# sismin.net
KiCad netlist of a schematic drawn in EAGLE
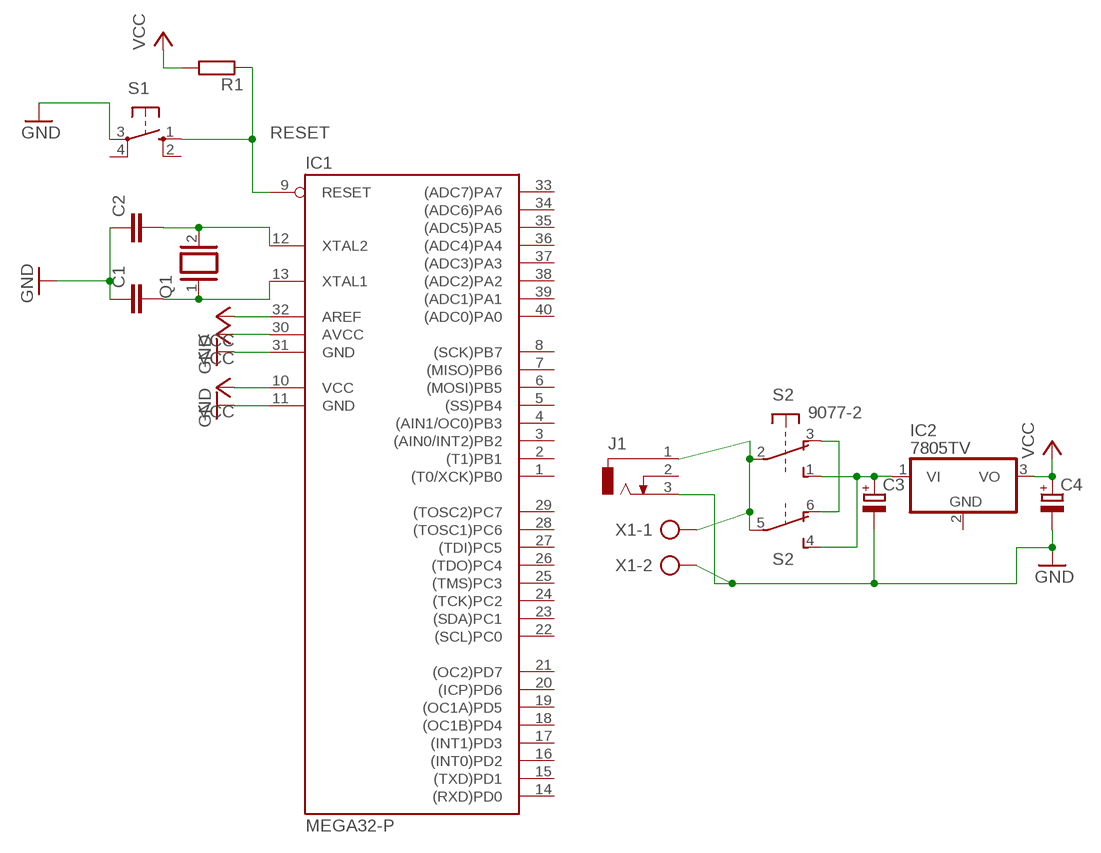
[diagram p0: schematic, sheet 1]

(export (version "E")
  (design (tool "Eeschema 10.0.6"))
  (components
    (comp (ref "C1")
      (value "C-EU025-025X050")
      (footprint "eagle-import:C025-025X050")
      (libsource (lib "eagle-import") (part "C-EU025-025X050"))
    )
    (comp (ref "C2")
      (value "C-EU025-025X050")
      (footprint "eagle-import:C025-025X050")
      (libsource (lib "eagle-import") (part "C-EU025-025X050"))
    )
    (comp (ref "C3")
      (value "CPOL-EUE2.5-5")
      (footprint "eagle-import:E2,5-5")
      (libsource (lib "eagle-import") (part "CPOL-EUE2.5-5"))
    )
    (comp (ref "C4")
      (value "CPOL-EUE2.5-5")
      (footprint "eagle-import:E2,5-5")
      (libsource (lib "eagle-import") (part "CPOL-EUE2.5-5"))
    )
    (comp (ref "IC1")
      (value "MEGA32-P")
      (footprint "eagle-import:DIL40")
      (fields (field (name "MPN") "ATMEGA32-16PU"))
      (libsource (lib "eagle-import") (part "MEGA32-P"))
    )
    (comp (ref "IC2")
      (value "7805TV")
      (footprint "eagle-import:TO220V")
      (libsource (lib "eagle-import") (part "78TV05"))
    )
    (comp (ref "J1")
      (value "DCJ0303")
      (footprint "eagle-import:DCJ0303")
      (libsource (lib "eagle-import") (part "DCJ0303"))
    )
    (comp (ref "Q1")
      (value "XTAL/S")
      (footprint "eagle-import:QS")
      (libsource (lib "eagle-import") (part "XTAL/S"))
    )
    (comp (ref "R1")
      (value "R-EU_0204/7")
      (footprint "eagle-import:0204_7")
      (libsource (lib "eagle-import") (part "R-EU_0204/7"))
    )
    (comp (ref "S1")
      (value "10-XX")
      (footprint "eagle-import:B3F-10XX")
      (fields (field (name "MPN") "B3F-1000"))
      (libsource (lib "eagle-import") (part "10-XX"))
    )
    (comp (ref "S2")
      (value "9077-2")
      (footprint "eagle-import:9077-2")
      (libsource (lib "eagle-import") (part "9077-2"))
    )
    (comp (ref "X1")
      (value "AK300/2")
      (footprint "eagle-import:AK300_2")
      (libsource (lib "eagle-import") (part "AK300/2"))
    )
  )
  (nets
    (net (code "1") (name "/RESET") (class "Default")
      (node (ref "IC1") (pin "9") (pinfunction "RESET_9") (pintype "input"))
      (node (ref "R1") (pin "1") (pinfunction "1_1") (pintype "passive"))
      (node (ref "S1") (pin "1") (pinfunction "S_1") (pintype "passive"))
    )
    (net (code "2") (name "GND") (class "Default")
      (node (ref "C1") (pin "1") (pinfunction "1_1") (pintype "passive"))
      (node (ref "C2") (pin "1") (pinfunction "1_1") (pintype "passive"))
      (node (ref "C3") (pin "-") (pinfunction "-_-") (pintype "passive"))
      (node (ref "C4") (pin "-") (pinfunction "-_-") (pintype "passive"))
      (node (ref "IC1") (pin "11") (pinfunction "GND_11") (pintype "power_in"))
      (node (ref "IC1") (pin "31") (pinfunction "GND_31") (pintype "power_in"))
      (node (ref "J1") (pin "3") (pinfunction "3_3") (pintype "passive"))
      (node (ref "S1") (pin "3") (pinfunction "P_3") (pintype "passive"))
      (node (ref "X1") (pin "2") (pinfunction "KL_2") (pintype "passive"))
    )
    (net (code "3") (name "Net-(IC1-XTAL1)") (class "Default")
      (node (ref "C1") (pin "2") (pinfunction "2_2") (pintype "passive"))
      (node (ref "IC1") (pin "13") (pinfunction "XTAL1_13") (pintype "bidirectional"))
      (node (ref "Q1") (pin "1") (pinfunction "1_1") (pintype "passive"))
    )
    (net (code "4") (name "Net-(IC1-XTAL2)") (class "Default")
      (node (ref "C2") (pin "2") (pinfunction "2_2") (pintype "passive"))
      (node (ref "IC1") (pin "12") (pinfunction "XTAL2_12") (pintype "bidirectional"))
      (node (ref "Q1") (pin "2") (pinfunction "2_2") (pintype "passive"))
    )
    (net (code "5") (name "Net-(IC2-VI)") (class "Default")
      (node (ref "C3") (pin "+") (pinfunction "+_+") (pintype "passive"))
      (node (ref "IC2") (pin "1") (pinfunction "VI_1") (pintype "input"))
      (node (ref "S2") (pin "1") (pinfunction "S_1") (pintype "passive"))
      (node (ref "S2") (pin "4") (pinfunction "S_4") (pintype "passive"))
    )
    (net (code "6") (name "Net-(S2A-O)") (class "Default")
      (node (ref "S2") (pin "3") (pinfunction "O_3") (pintype "passive"))
      (node (ref "S2") (pin "6") (pinfunction "O_6") (pintype "passive"))
    )
    (net (code "7") (name "Net-(S2A-P)") (class "Default")
      (node (ref "J1") (pin "1") (pinfunction "1_1") (pintype "passive"))
      (node (ref "S2") (pin "2") (pinfunction "P_2") (pintype "passive"))
      (node (ref "S2") (pin "5") (pinfunction "P_5") (pintype "passive"))
      (node (ref "X1") (pin "1") (pinfunction "KL_1") (pintype "passive"))
    )
    (net (code "8") (name "VCC") (class "Default")
      (node (ref "C4") (pin "+") (pinfunction "+_+") (pintype "passive"))
      (node (ref "IC1") (pin "10") (pinfunction "VCC_10") (pintype "power_in"))
      (node (ref "IC1") (pin "30") (pinfunction "AVCC_30") (pintype "power_in"))
      (node (ref "IC1") (pin "32") (pinfunction "AREF_32") (pintype "passive"))
      (node (ref "IC2") (pin "3") (pinfunction "VO_3") (pintype "passive"))
      (node (ref "R1") (pin "2") (pinfunction "2_2") (pintype "passive"))
    )
    (net (code "9") (name "unconnected-(IC1-(ADC0)PA0-Pad40)") (class "Default")
      (node (ref "IC1") (pin "40") (pinfunction "(ADC0)PA0_40") (pintype "bidirectional"))
    )
    (net (code "10") (name "unconnected-(IC1-(ADC1)PA1-Pad39)") (class "Default")
      (node (ref "IC1") (pin "39") (pinfunction "(ADC1)PA1_39") (pintype "bidirectional"))
    )
    (net (code "11") (name "unconnected-(IC1-(ADC2)PA2-Pad38)") (class "Default")
      (node (ref "IC1") (pin "38") (pinfunction "(ADC2)PA2_38") (pintype "bidirectional"))
    )
    (net (code "12") (name "unconnected-(IC1-(ADC3)PA3-Pad37)") (class "Default")
      (node (ref "IC1") (pin "37") (pinfunction "(ADC3)PA3_37") (pintype "bidirectional"))
    )
    (net (code "13") (name "unconnected-(IC1-(ADC4)PA4-Pad36)") (class "Default")
      (node (ref "IC1") (pin "36") (pinfunction "(ADC4)PA4_36") (pintype "bidirectional"))
    )
    (net (code "14") (name "unconnected-(IC1-(ADC5)PA5-Pad35)") (class "Default")
      (node (ref "IC1") (pin "35") (pinfunction "(ADC5)PA5_35") (pintype "bidirectional"))
    )
    (net (code "15") (name "unconnected-(IC1-(ADC6)PA6-Pad34)") (class "Default")
      (node (ref "IC1") (pin "34") (pinfunction "(ADC6)PA6_34") (pintype "bidirectional"))
    )
    (net (code "16") (name "unconnected-(IC1-(ADC7)PA7-Pad33)") (class "Default")
      (node (ref "IC1") (pin "33") (pinfunction "(ADC7)PA7_33") (pintype "bidirectional"))
    )
    (net (code "17") (name "unconnected-(IC1-(AIN0{slash}INT2)PB2-Pad3)") (class "Default")
      (node (ref "IC1") (pin "3") (pinfunction "(AIN0/INT2)PB2_3") (pintype "bidirectional"))
    )
    (net (code "18") (name "unconnected-(IC1-(AIN1{slash}OC0)PB3-Pad4)") (class "Default")
      (node (ref "IC1") (pin "4") (pinfunction "(AIN1/OC0)PB3_4") (pintype "bidirectional"))
    )
    (net (code "19") (name "unconnected-(IC1-(ICP)PD6-Pad20)") (class "Default")
      (node (ref "IC1") (pin "20") (pinfunction "(ICP)PD6_20") (pintype "bidirectional"))
    )
    (net (code "20") (name "unconnected-(IC1-(INT0)PD2-Pad16)") (class "Default")
      (node (ref "IC1") (pin "16") (pinfunction "(INT0)PD2_16") (pintype "bidirectional"))
    )
    (net (code "21") (name "unconnected-(IC1-(INT1)PD3-Pad17)") (class "Default")
      (node (ref "IC1") (pin "17") (pinfunction "(INT1)PD3_17") (pintype "bidirectional"))
    )
    (net (code "22") (name "unconnected-(IC1-(MISO)PB6-Pad7)") (class "Default")
      (node (ref "IC1") (pin "7") (pinfunction "(MISO)PB6_7") (pintype "bidirectional"))
    )
    (net (code "23") (name "unconnected-(IC1-(MOSI)PB5-Pad6)") (class "Default")
      (node (ref "IC1") (pin "6") (pinfunction "(MOSI)PB5_6") (pintype "bidirectional"))
    )
    (net (code "24") (name "unconnected-(IC1-(OC1A)PD5-Pad19)") (class "Default")
      (node (ref "IC1") (pin "19") (pinfunction "(OC1A)PD5_19") (pintype "bidirectional"))
    )
    (net (code "25") (name "unconnected-(IC1-(OC1B)PD4-Pad18)") (class "Default")
      (node (ref "IC1") (pin "18") (pinfunction "(OC1B)PD4_18") (pintype "bidirectional"))
    )
    (net (code "26") (name "unconnected-(IC1-(OC2)PD7-Pad21)") (class "Default")
      (node (ref "IC1") (pin "21") (pinfunction "(OC2)PD7_21") (pintype "bidirectional"))
    )
    (net (code "27") (name "unconnected-(IC1-(RXD)PD0-Pad14)") (class "Default")
      (node (ref "IC1") (pin "14") (pinfunction "(RXD)PD0_14") (pintype "bidirectional"))
    )
    (net (code "28") (name "unconnected-(IC1-(SCK)PB7-Pad8)") (class "Default")
      (node (ref "IC1") (pin "8") (pinfunction "(SCK)PB7_8") (pintype "bidirectional"))
    )
    (net (code "29") (name "unconnected-(IC1-(SCL)PC0-Pad22)") (class "Default")
      (node (ref "IC1") (pin "22") (pinfunction "(SCL)PC0_22") (pintype "bidirectional"))
    )
    (net (code "30") (name "unconnected-(IC1-(SDA)PC1-Pad23)") (class "Default")
      (node (ref "IC1") (pin "23") (pinfunction "(SDA)PC1_23") (pintype "bidirectional"))
    )
    (net (code "31") (name "unconnected-(IC1-(SS)PB4-Pad5)") (class "Default")
      (node (ref "IC1") (pin "5") (pinfunction "(SS)PB4_5") (pintype "bidirectional"))
    )
    (net (code "32") (name "unconnected-(IC1-(T0{slash}XCK)PB0-Pad1)") (class "Default")
      (node (ref "IC1") (pin "1") (pinfunction "(T0/XCK)PB0_1") (pintype "bidirectional"))
    )
    (net (code "33") (name "unconnected-(IC1-(T1)PB1-Pad2)") (class "Default")
      (node (ref "IC1") (pin "2") (pinfunction "(T1)PB1_2") (pintype "bidirectional"))
    )
    (net (code "34") (name "unconnected-(IC1-(TCK)PC2-Pad24)") (class "Default")
      (node (ref "IC1") (pin "24") (pinfunction "(TCK)PC2_24") (pintype "bidirectional"))
    )
    (net (code "35") (name "unconnected-(IC1-(TDI)PC5-Pad27)") (class "Default")
      (node (ref "IC1") (pin "27") (pinfunction "(TDI)PC5_27") (pintype "bidirectional"))
    )
    (net (code "36") (name "unconnected-(IC1-(TDO)PC4-Pad26)") (class "Default")
      (node (ref "IC1") (pin "26") (pinfunction "(TDO)PC4_26") (pintype "bidirectional"))
    )
    (net (code "37") (name "unconnected-(IC1-(TMS)PC3-Pad25)") (class "Default")
      (node (ref "IC1") (pin "25") (pinfunction "(TMS)PC3_25") (pintype "bidirectional"))
    )
    (net (code "38") (name "unconnected-(IC1-(TOSC1)PC6-Pad28)") (class "Default")
      (node (ref "IC1") (pin "28") (pinfunction "(TOSC1)PC6_28") (pintype "bidirectional"))
    )
    (net (code "39") (name "unconnected-(IC1-(TOSC2)PC7-Pad29)") (class "Default")
      (node (ref "IC1") (pin "29") (pinfunction "(TOSC2)PC7_29") (pintype "bidirectional"))
    )
    (net (code "40") (name "unconnected-(IC1-(TXD)PD1-Pad15)") (class "Default")
      (node (ref "IC1") (pin "15") (pinfunction "(TXD)PD1_15") (pintype "bidirectional"))
    )
    (net (code "41") (name "unconnected-(IC2-GND-Pad2)") (class "Default")
      (node (ref "IC2") (pin "2") (pinfunction "GND_2") (pintype "passive"))
    )
    (net (code "42") (name "unconnected-(J1-Pad2)") (class "Default")
      (node (ref "J1") (pin "2") (pinfunction "2_2") (pintype "passive"))
    )
    (net (code "43") (name "unconnected-(S1-P1-Pad4)") (class "Default")
      (node (ref "S1") (pin "4") (pinfunction "P1_4") (pintype "passive"))
    )
    (net (code "44") (name "unconnected-(S1-S1-Pad2)") (class "Default")
      (node (ref "S1") (pin "2") (pinfunction "S1_2") (pintype "passive"))
    )
  )
)
